# cap_bank.net
KiCad netlist of a schematic drawn in Altium Designer
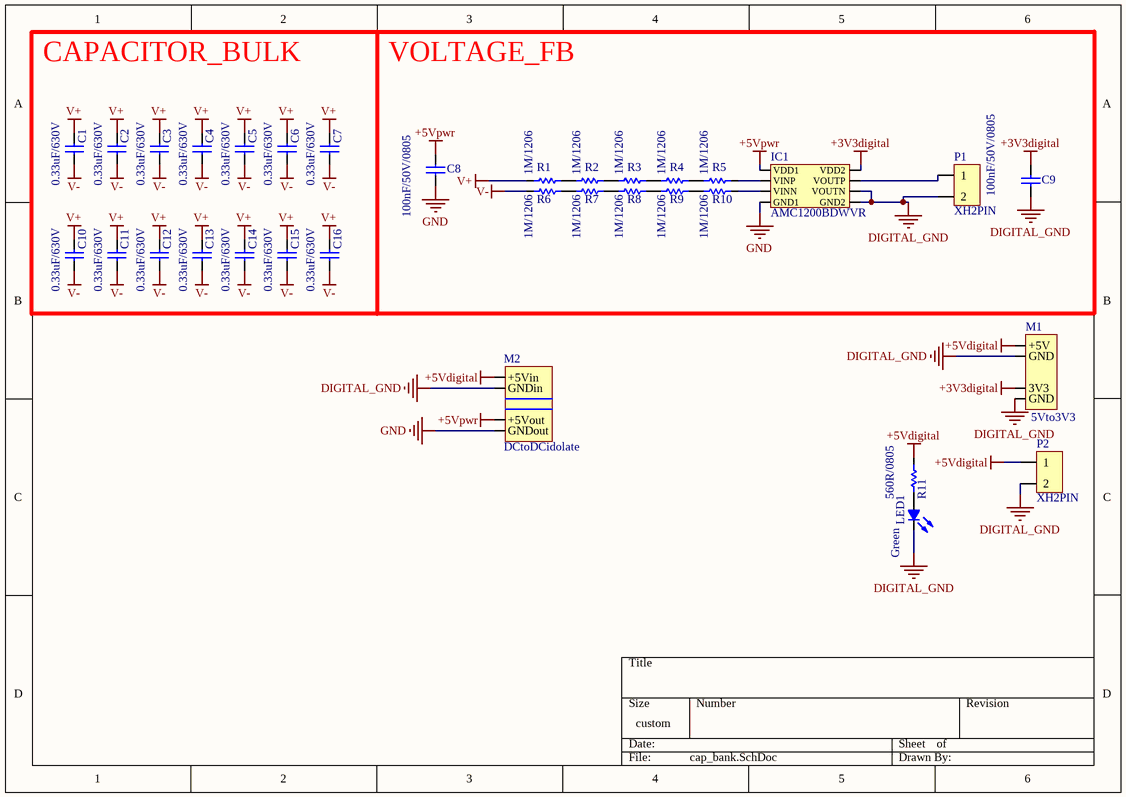
[diagram p0: cap_bank.SchDoc]

(export (version "E")
  (design (tool "Eeschema 10.0.6"))
  (components
    (comp (ref "C1")
      (value "0.33uF/630V")
      (footprint "0.33uF/630V")
      (description "Capacitor")
      (libsource (lib "Schlib") (part "Capacitor"))
    )
    (comp (ref "C2")
      (value "0.33uF/630V")
      (footprint "0.33uF/630V")
      (description "Capacitor")
      (libsource (lib "Schlib") (part "Capacitor"))
    )
    (comp (ref "C3")
      (value "0.33uF/630V")
      (footprint "0.33uF/630V")
      (description "Capacitor")
      (libsource (lib "Schlib") (part "Capacitor"))
    )
    (comp (ref "C4")
      (value "0.33uF/630V")
      (footprint "0.33uF/630V")
      (description "Capacitor")
      (libsource (lib "Schlib") (part "Capacitor"))
    )
    (comp (ref "C5")
      (value "0.33uF/630V")
      (footprint "0.33uF/630V")
      (description "Capacitor")
      (libsource (lib "Schlib") (part "Capacitor"))
    )
    (comp (ref "C6")
      (value "0.33uF/630V")
      (footprint "0.33uF/630V")
      (description "Capacitor")
      (libsource (lib "Schlib") (part "Capacitor"))
    )
    (comp (ref "C7")
      (value "0.33uF/630V")
      (footprint "0.33uF/630V")
      (description "Capacitor")
      (libsource (lib "Schlib") (part "Capacitor"))
    )
    (comp (ref "C8")
      (value "100nF/50V/0805")
      (footprint "CAP 0805")
      (description "Capacitor")
      (libsource (lib "Schlib") (part "Capacitor"))
    )
    (comp (ref "C9")
      (value "100nF/50V/0805")
      (footprint "CAP 0805")
      (description "Capacitor")
      (libsource (lib "Schlib") (part "Capacitor"))
    )
    (comp (ref "C10")
      (value "0.33uF/630V")
      (footprint "0.33uF/630V")
      (description "Capacitor")
      (libsource (lib "Schlib") (part "Capacitor"))
    )
    (comp (ref "C11")
      (value "0.33uF/630V")
      (footprint "0.33uF/630V")
      (description "Capacitor")
      (libsource (lib "Schlib") (part "Capacitor"))
    )
    (comp (ref "C12")
      (value "0.33uF/630V")
      (footprint "0.33uF/630V")
      (description "Capacitor")
      (libsource (lib "Schlib") (part "Capacitor"))
    )
    (comp (ref "C13")
      (value "0.33uF/630V")
      (footprint "0.33uF/630V")
      (description "Capacitor")
      (libsource (lib "Schlib") (part "Capacitor"))
    )
    (comp (ref "C14")
      (value "0.33uF/630V")
      (footprint "0.33uF/630V")
      (description "Capacitor")
      (libsource (lib "Schlib") (part "Capacitor"))
    )
    (comp (ref "C15")
      (value "0.33uF/630V")
      (footprint "0.33uF/630V")
      (description "Capacitor")
      (libsource (lib "Schlib") (part "Capacitor"))
    )
    (comp (ref "C16")
      (value "0.33uF/630V")
      (footprint "0.33uF/630V")
      (description "Capacitor")
      (libsource (lib "Schlib") (part "Capacitor"))
    )
    (comp (ref "IC1")
      (value "AMC1200BDWVR")
      (footprint "SOIC8-AMC1200")
      (description "isolate op-amp g = 8")
      (libsource (lib "Schlib") (part "AMC1200BDWVR"))
    )
    (comp (ref "LED1")
      (value "LED 3mm/Green")
      (footprint "LED 3mm")
      (description "Typical LED")
      (fields (field (name "COLOR") "Green"))
      (libsource (lib "TL494 12V-20A-KARA") (part "LED"))
    )
    (comp (ref "M1") (value "5Vto3V3") (footprint "5Vto3V3") (libsource (lib "Schlib") (part "5Vto3V3")))
    (comp (ref "M2")
      (value "DCtoDCidolate")
      (footprint "dctodc")
      (libsource (lib "Schlib") (part "DCtoDCidolate"))
    )
    (comp (ref "P1")
      (value "XH2PIN")
      (footprint "XH-2Pin")
      (description "RELAY")
      (fields (field (name "PUBLISHER") "Altium Limited"))
      (libsource (lib "Schlib") (part "Header 2H"))
    )
    (comp (ref "P2")
      (value "XH2PIN")
      (footprint "XH-2Pin")
      (description "RELAY")
      (fields (field (name "PUBLISHER") "Altium Limited"))
      (libsource (lib "Schlib") (part "Header 2H"))
    )
    (comp (ref "R1") (value "1M/1206") (footprint "RES 1206") (libsource (lib "Schlib") (part "Res")))
    (comp (ref "R2") (value "1M/1206") (footprint "RES 1206") (libsource (lib "Schlib") (part "Res")))
    (comp (ref "R3") (value "1M/1206") (footprint "RES 1206") (libsource (lib "Schlib") (part "Res")))
    (comp (ref "R4") (value "1M/1206") (footprint "RES 1206") (libsource (lib "Schlib") (part "Res")))
    (comp (ref "R5") (value "1M/1206") (footprint "RES 1206") (libsource (lib "Schlib") (part "Res")))
    (comp (ref "R6") (value "1M/1206") (footprint "RES 1206") (libsource (lib "Schlib") (part "Res")))
    (comp (ref "R7") (value "1M/1206") (footprint "RES 1206") (libsource (lib "Schlib") (part "Res")))
    (comp (ref "R8") (value "1M/1206") (footprint "RES 1206") (libsource (lib "Schlib") (part "Res")))
    (comp (ref "R9") (value "1M/1206") (footprint "RES 1206") (libsource (lib "Schlib") (part "Res")))
    (comp (ref "R10") (value "1M/1206") (footprint "RES 1206") (libsource (lib "Schlib") (part "Res")))
    (comp (ref "R11") (value "560R/0805") (footprint "RES 0805") (libsource (lib "Schlib") (part "Res")))
  )
  (nets
    (net (code "1") (name "+3V3digital") (class "Default")
      (node (ref "C9") (pin "1") (pinfunction "+_1") (pintype "passive"))
      (node (ref "IC1") (pin "8") (pinfunction "VDD2_8") (pintype "passive"))
      (node (ref "M1") (pin "3") (pinfunction "3V3_3") (pintype "passive"))
    )
    (net (code "2") (name "+5Vdigital") (class "Default")
      (node (ref "M1") (pin "1") (pinfunction "+5V_1") (pintype "passive"))
      (node (ref "M2") (pin "1") (pinfunction "+5Vin_1") (pintype "passive"))
      (node (ref "P2") (pin "1") (pinfunction "1_1") (pintype "passive"))
      (node (ref "R11") (pin "2") (pinfunction "2_2") (pintype "passive"))
    )
    (net (code "3") (name "+5Vpwr") (class "Default")
      (node (ref "C8") (pin "1") (pinfunction "+_1") (pintype "passive"))
      (node (ref "IC1") (pin "1") (pinfunction "VDD1_1") (pintype "passive"))
      (node (ref "M2") (pin "3") (pinfunction "+5Vout_3") (pintype "passive"))
    )
    (net (code "4") (name "DIGITAL_GND") (class "Default")
      (node (ref "C9") (pin "2") (pinfunction "-_2") (pintype "passive"))
      (node (ref "IC1") (pin "5") (pinfunction "GND2_5") (pintype "passive"))
      (node (ref "IC1") (pin "6") (pinfunction "VOUTN_6") (pintype "passive"))
      (node (ref "LED1") (pin "2") (pinfunction "K_2") (pintype "passive"))
      (node (ref "M1") (pin "2") (pinfunction "GND_2") (pintype "passive"))
      (node (ref "M1") (pin "4") (pinfunction "GND_4") (pintype "passive"))
      (node (ref "M2") (pin "2") (pinfunction "GNDin_2") (pintype "passive"))
      (node (ref "P1") (pin "2") (pinfunction "2_2") (pintype "passive"))
      (node (ref "P2") (pin "2") (pinfunction "2_2") (pintype "passive"))
    )
    (net (code "5") (name "GND") (class "Default")
      (node (ref "C8") (pin "2") (pinfunction "-_2") (pintype "passive"))
      (node (ref "IC1") (pin "4") (pinfunction "GND1_4") (pintype "passive"))
      (node (ref "M2") (pin "4") (pinfunction "GNDout_4") (pintype "passive"))
    )
    (net (code "6") (name "Net-(IC1-VINN)") (class "Default")
      (node (ref "IC1") (pin "3") (pinfunction "VINN_3") (pintype "passive"))
      (node (ref "R10") (pin "2") (pinfunction "2_2") (pintype "passive"))
    )
    (net (code "7") (name "Net-(IC1-VINP)") (class "Default")
      (node (ref "IC1") (pin "2") (pinfunction "VINP_2") (pintype "passive"))
      (node (ref "R5") (pin "2") (pinfunction "2_2") (pintype "passive"))
    )
    (net (code "8") (name "Net-(IC1-VOUTP)") (class "Default")
      (node (ref "IC1") (pin "7") (pinfunction "VOUTP_7") (pintype "passive"))
      (node (ref "P1") (pin "1") (pinfunction "1_1") (pintype "passive"))
    )
    (net (code "9") (name "Net-(LED1-A)") (class "Default")
      (node (ref "LED1") (pin "1") (pinfunction "A_1") (pintype "passive"))
      (node (ref "R11") (pin "1") (pinfunction "1_1") (pintype "passive"))
    )
    (net (code "10") (name "Net-(R1-Pad2)") (class "Default")
      (node (ref "R1") (pin "2") (pinfunction "2_2") (pintype "passive"))
      (node (ref "R2") (pin "1") (pinfunction "1_1") (pintype "passive"))
    )
    (net (code "11") (name "Net-(R2-Pad2)") (class "Default")
      (node (ref "R2") (pin "2") (pinfunction "2_2") (pintype "passive"))
      (node (ref "R3") (pin "1") (pinfunction "1_1") (pintype "passive"))
    )
    (net (code "12") (name "Net-(R3-Pad2)") (class "Default")
      (node (ref "R3") (pin "2") (pinfunction "2_2") (pintype "passive"))
      (node (ref "R4") (pin "1") (pinfunction "1_1") (pintype "passive"))
    )
    (net (code "13") (name "Net-(R4-Pad2)") (class "Default")
      (node (ref "R4") (pin "2") (pinfunction "2_2") (pintype "passive"))
      (node (ref "R5") (pin "1") (pinfunction "1_1") (pintype "passive"))
    )
    (net (code "14") (name "Net-(R6-Pad2)") (class "Default")
      (node (ref "R6") (pin "2") (pinfunction "2_2") (pintype "passive"))
      (node (ref "R7") (pin "1") (pinfunction "1_1") (pintype "passive"))
    )
    (net (code "15") (name "Net-(R7-Pad2)") (class "Default")
      (node (ref "R7") (pin "2") (pinfunction "2_2") (pintype "passive"))
      (node (ref "R8") (pin "1") (pinfunction "1_1") (pintype "passive"))
    )
    (net (code "16") (name "Net-(R8-Pad2)") (class "Default")
      (node (ref "R8") (pin "2") (pinfunction "2_2") (pintype "passive"))
      (node (ref "R9") (pin "1") (pinfunction "1_1") (pintype "passive"))
    )
    (net (code "17") (name "Net-(R10-Pad1)") (class "Default")
      (node (ref "R10") (pin "1") (pinfunction "1_1") (pintype "passive"))
      (node (ref "R9") (pin "2") (pinfunction "2_2") (pintype "passive"))
    )
    (net (code "18") (name "V+") (class "Default")
      (node (ref "C1") (pin "1") (pinfunction "+_1") (pintype "passive"))
      (node (ref "C10") (pin "1") (pinfunction "+_1") (pintype "passive"))
      (node (ref "C11") (pin "1") (pinfunction "+_1") (pintype "passive"))
      (node (ref "C12") (pin "1") (pinfunction "+_1") (pintype "passive"))
      (node (ref "C13") (pin "1") (pinfunction "+_1") (pintype "passive"))
      (node (ref "C14") (pin "1") (pinfunction "+_1") (pintype "passive"))
      (node (ref "C15") (pin "1") (pinfunction "+_1") (pintype "passive"))
      (node (ref "C16") (pin "1") (pinfunction "+_1") (pintype "passive"))
      (node (ref "C2") (pin "1") (pinfunction "+_1") (pintype "passive"))
      (node (ref "C3") (pin "1") (pinfunction "+_1") (pintype "passive"))
      (node (ref "C4") (pin "1") (pinfunction "+_1") (pintype "passive"))
      (node (ref "C5") (pin "1") (pinfunction "+_1") (pintype "passive"))
      (node (ref "C6") (pin "1") (pinfunction "+_1") (pintype "passive"))
      (node (ref "C7") (pin "1") (pinfunction "+_1") (pintype "passive"))
      (node (ref "R1") (pin "1") (pinfunction "1_1") (pintype "passive"))
    )
    (net (code "19") (name "V-") (class "Default")
      (node (ref "C1") (pin "2") (pinfunction "-_2") (pintype "passive"))
      (node (ref "C10") (pin "2") (pinfunction "-_2") (pintype "passive"))
      (node (ref "C11") (pin "2") (pinfunction "-_2") (pintype "passive"))
      (node (ref "C12") (pin "2") (pinfunction "-_2") (pintype "passive"))
      (node (ref "C13") (pin "2") (pinfunction "-_2") (pintype "passive"))
      (node (ref "C14") (pin "2") (pinfunction "-_2") (pintype "passive"))
      (node (ref "C15") (pin "2") (pinfunction "-_2") (pintype "passive"))
      (node (ref "C16") (pin "2") (pinfunction "-_2") (pintype "passive"))
      (node (ref "C2") (pin "2") (pinfunction "-_2") (pintype "passive"))
      (node (ref "C3") (pin "2") (pinfunction "-_2") (pintype "passive"))
      (node (ref "C4") (pin "2") (pinfunction "-_2") (pintype "passive"))
      (node (ref "C5") (pin "2") (pinfunction "-_2") (pintype "passive"))
      (node (ref "C6") (pin "2") (pinfunction "-_2") (pintype "passive"))
      (node (ref "C7") (pin "2") (pinfunction "-_2") (pintype "passive"))
      (node (ref "R6") (pin "1") (pinfunction "1_1") (pintype "passive"))
    )
  )
)
